# DotLight.net
KiCad netlist of a schematic drawn in EAGLE
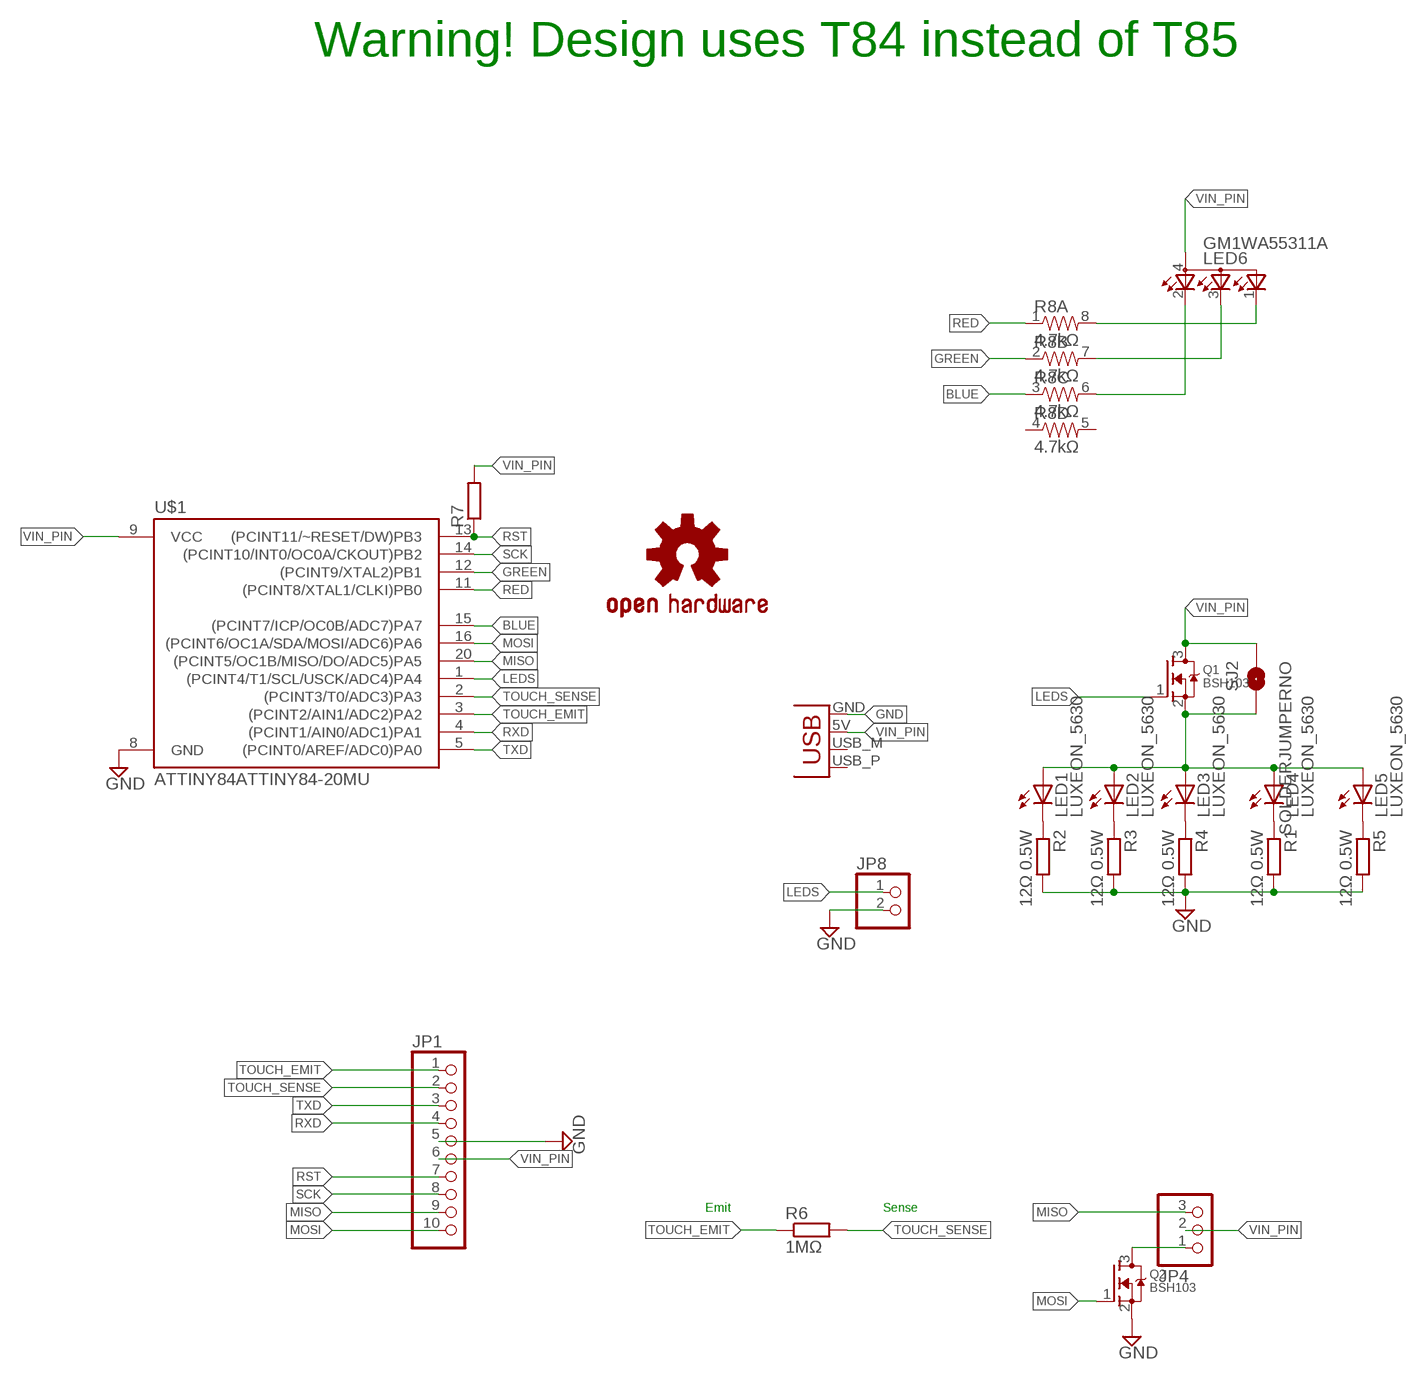
[diagram p0: schematic, sheet 1]
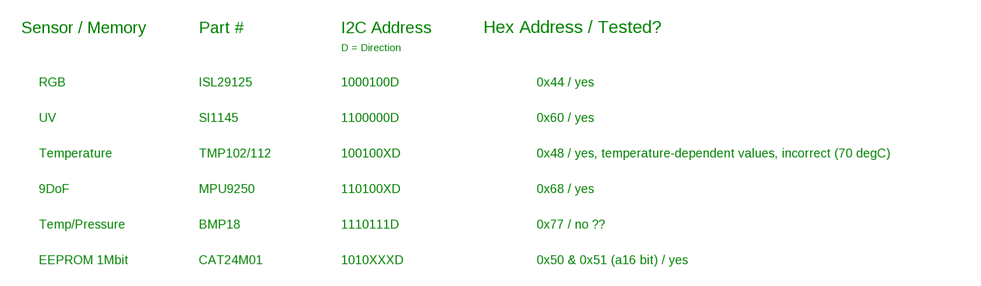
[diagram p1: schematic, sheet 2]
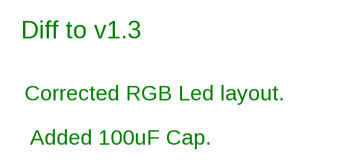
[diagram p2: schematic, sheet 3]

(export (version "E")
  (design (tool "Eeschema 10.0.6"))
  (components
    (comp (ref "JP1")
      (value "PINHD-1X10")
      (footprint "eagle-import:1X10")
      (libsource (lib "eagle-import") (part "PINHD-1X10"))
    )
    (comp (ref "JP3")
      (value "USBPCB")
      (footprint "eagle-import:USB-A-PCB")
      (libsource (lib "eagle-import") (part "USBPCB"))
    )
    (comp (ref "JP4")
      (value "PINHD-1X3")
      (footprint "eagle-import:1X03")
      (libsource (lib "eagle-import") (part "PINHD-1X3"))
    )
    (comp (ref "JP8")
      (value "PINHD-1X2")
      (footprint "eagle-import:1X02")
      (libsource (lib "eagle-import") (part "PINHD-1X2"))
    )
    (comp (ref "LED1")
      (value "LUXEON_5630")
      (footprint "eagle-import:LUXEON_5630")
      (libsource (lib "eagle-import") (part "LUXEON_5630"))
    )
    (comp (ref "LED2")
      (value "LUXEON_5630")
      (footprint "eagle-import:LUXEON_5630")
      (libsource (lib "eagle-import") (part "LUXEON_5630"))
    )
    (comp (ref "LED3")
      (value "LUXEON_5630")
      (footprint "eagle-import:LUXEON_5630")
      (libsource (lib "eagle-import") (part "LUXEON_5630"))
    )
    (comp (ref "LED4")
      (value "LUXEON_5630")
      (footprint "eagle-import:LUXEON_5630")
      (libsource (lib "eagle-import") (part "LUXEON_5630"))
    )
    (comp (ref "LED5")
      (value "LUXEON_5630")
      (footprint "eagle-import:LUXEON_5630")
      (libsource (lib "eagle-import") (part "LUXEON_5630"))
    )
    (comp (ref "LED6")
      (value "GM1WA55311A")
      (footprint "eagle-import:GM1WA55311A")
      (libsource (lib "eagle-import") (part "GM1WA55311A"))
    )
    (comp (ref "LOGO1")
      (value "OSHW-LOGOS")
      (footprint "eagle-import:OSHW-LOGO-S")
      (libsource (lib "eagle-import") (part "OSHW-LOGOS"))
    )
    (comp (ref "Q1")
      (value "BSH103")
      (footprint "eagle-import:SOT23")
      (libsource (lib "eagle-import") (part "MOSFET-NREFLOW"))
    )
    (comp (ref "Q2")
      (value "BSH103")
      (footprint "eagle-import:SOT23")
      (libsource (lib "eagle-import") (part "MOSFET-NREFLOW"))
    )
    (comp (ref "R1")
      (value "12Ω 0.5W")
      (footprint "eagle-import:R1210")
      (libsource (lib "eagle-import") (part "resistor_R-EU_R1210"))
    )
    (comp (ref "R2")
      (value "12Ω 0.5W")
      (footprint "eagle-import:R1210")
      (libsource (lib "eagle-import") (part "resistor_R-EU_R1210"))
    )
    (comp (ref "R3")
      (value "12Ω 0.5W")
      (footprint "eagle-import:R1210")
      (libsource (lib "eagle-import") (part "resistor_R-EU_R1210"))
    )
    (comp (ref "R4")
      (value "12Ω 0.5W")
      (footprint "eagle-import:R1210")
      (libsource (lib "eagle-import") (part "resistor_R-EU_R1210"))
    )
    (comp (ref "R5")
      (value "12Ω 0.5W")
      (footprint "eagle-import:R1210")
      (libsource (lib "eagle-import") (part "resistor_R-EU_R1210"))
    )
    (comp (ref "R6")
      (value "1MΩ")
      (footprint "eagle-import:R1206")
      (libsource (lib "eagle-import") (part "resistor_R-EU_R1206"))
    )
    (comp (ref "R7")
      (value "R-EU_R0603")
      (footprint "eagle-import:R0603")
      (libsource (lib "eagle-import") (part "R-EU_R0603"))
    )
    (comp (ref "R8")
      (value "4.7kΩ")
      (footprint "eagle-import:0603-ARV")
      (libsource (lib "eagle-import") (part "RESISTOR-ARRAY0603-ARV"))
    )
    (comp (ref "SJ2")
      (value "SOLDERJUMPERNO")
      (footprint "eagle-import:SJ_2S-NO")
      (libsource (lib "eagle-import") (part "SOLDERJUMPERNO"))
    )
    (comp (ref "U$1")
      (value "ATTINY84ATTINY84-20MU")
      (footprint "eagle-import:QFN20")
      (libsource (lib "eagle-import") (part "ATTINY84ATTINY84-20MU"))
    )
  )
  (nets
    (net (code "1") (name "BLUE") (class "Default")
      (node (ref "R8") (pin "3") (pinfunction "1_3") (pintype "passive"))
      (node (ref "U$1") (pin "15") (pinfunction "(PCINT7/ICP/OC0B/ADC7)PA7_15") (pintype "bidirectional"))
    )
    (net (code "2") (name "GND") (class "Default")
      (node (ref "JP1") (pin "5") (pinfunction "5_5") (pintype "passive"))
      (node (ref "JP3") (pin "GND") (pinfunction "GND_GND") (pintype "bidirectional"))
      (node (ref "JP8") (pin "2") (pinfunction "2_2") (pintype "passive"))
      (node (ref "Q2") (pin "2") (pinfunction "S_2") (pintype "bidirectional"))
      (node (ref "R1") (pin "2") (pinfunction "2_2") (pintype "passive"))
      (node (ref "R2") (pin "2") (pinfunction "2_2") (pintype "passive"))
      (node (ref "R3") (pin "2") (pinfunction "2_2") (pintype "passive"))
      (node (ref "R4") (pin "2") (pinfunction "2_2") (pintype "passive"))
      (node (ref "R5") (pin "2") (pinfunction "2_2") (pintype "passive"))
      (node (ref "U$1") (pin "8") (pinfunction "GND_8") (pintype "bidirectional"))
    )
    (net (code "3") (name "GREEN") (class "Default")
      (node (ref "R8") (pin "2") (pinfunction "1_2") (pintype "passive"))
      (node (ref "U$1") (pin "12") (pinfunction "(PCINT9/XTAL2)PB1_12") (pintype "bidirectional"))
    )
    (net (code "4") (name "LEDS") (class "Default")
      (node (ref "JP8") (pin "1") (pinfunction "1_1") (pintype "passive"))
      (node (ref "Q1") (pin "1") (pinfunction "G_1") (pintype "bidirectional"))
      (node (ref "U$1") (pin "1") (pinfunction "(PCINT4/T1/SCL/USCK/ADC4)PA4_1") (pintype "bidirectional"))
    )
    (net (code "5") (name "MISO") (class "Default")
      (node (ref "JP1") (pin "9") (pinfunction "9_9") (pintype "passive"))
      (node (ref "JP4") (pin "3") (pinfunction "3_3") (pintype "passive"))
      (node (ref "U$1") (pin "20") (pinfunction "(PCINT5/OC1B/MISO/DO/ADC5)PA5_20") (pintype "bidirectional"))
    )
    (net (code "6") (name "MOSI") (class "Default")
      (node (ref "JP1") (pin "10") (pinfunction "10_10") (pintype "passive"))
      (node (ref "Q2") (pin "1") (pinfunction "G_1") (pintype "bidirectional"))
      (node (ref "U$1") (pin "16") (pinfunction "(PCINT6/OC1A/SDA/MOSI/ADC6)PA6_16") (pintype "bidirectional"))
    )
    (net (code "7") (name "Net-(LED1-PadC)") (class "Default")
      (node (ref "LED1") (pin "C") (pinfunction "C_C") (pintype "passive"))
      (node (ref "R2") (pin "1") (pinfunction "1_1") (pintype "passive"))
    )
    (net (code "8") (name "Net-(LED2-PadC)") (class "Default")
      (node (ref "LED2") (pin "C") (pinfunction "C_C") (pintype "passive"))
      (node (ref "R3") (pin "1") (pinfunction "1_1") (pintype "passive"))
    )
    (net (code "9") (name "Net-(LED3-PadC)") (class "Default")
      (node (ref "LED3") (pin "C") (pinfunction "C_C") (pintype "passive"))
      (node (ref "R4") (pin "1") (pinfunction "1_1") (pintype "passive"))
    )
    (net (code "10") (name "Net-(LED4-PadC)") (class "Default")
      (node (ref "LED4") (pin "C") (pinfunction "C_C") (pintype "passive"))
      (node (ref "R1") (pin "1") (pinfunction "1_1") (pintype "passive"))
    )
    (net (code "11") (name "Net-(LED5-PadC)") (class "Default")
      (node (ref "LED5") (pin "C") (pinfunction "C_C") (pintype "passive"))
      (node (ref "R5") (pin "1") (pinfunction "1_1") (pintype "passive"))
    )
    (net (code "12") (name "Net-(LED6-CBLUE)") (class "Default")
      (node (ref "LED6") (pin "3") (pinfunction "CBLUE_3") (pintype "passive"))
      (node (ref "R8") (pin "7") (pinfunction "2_7") (pintype "passive"))
    )
    (net (code "13") (name "Net-(LED6-CGREEN)") (class "Default")
      (node (ref "LED6") (pin "1") (pinfunction "CGREEN_1") (pintype "passive"))
      (node (ref "R8") (pin "8") (pinfunction "2_8") (pintype "passive"))
    )
    (net (code "14") (name "Net-(LED6-CRED)") (class "Default")
      (node (ref "LED6") (pin "2") (pinfunction "CRED_2") (pintype "passive"))
      (node (ref "R8") (pin "6") (pinfunction "2_6") (pintype "passive"))
    )
    (net (code "15") (name "Net-(Q1-S)") (class "Default")
      (node (ref "LED1") (pin "A") (pinfunction "A_A") (pintype "passive"))
      (node (ref "LED2") (pin "A") (pinfunction "A_A") (pintype "passive"))
      (node (ref "LED3") (pin "A") (pinfunction "A_A") (pintype "passive"))
      (node (ref "LED4") (pin "A") (pinfunction "A_A") (pintype "passive"))
      (node (ref "LED5") (pin "A") (pinfunction "A_A") (pintype "passive"))
      (node (ref "Q1") (pin "2") (pinfunction "S_2") (pintype "bidirectional"))
      (node (ref "SJ2") (pin "2") (pinfunction "2_2") (pintype "passive"))
    )
    (net (code "16") (name "Net-(Q2-D)") (class "Default")
      (node (ref "JP4") (pin "1") (pinfunction "1_1") (pintype "passive"))
      (node (ref "Q2") (pin "3") (pinfunction "D_3") (pintype "bidirectional"))
    )
    (net (code "17") (name "RED") (class "Default")
      (node (ref "R8") (pin "1") (pinfunction "1_1") (pintype "passive"))
      (node (ref "U$1") (pin "11") (pinfunction "(PCINT8/XTAL1/CLKI)PB0_11") (pintype "bidirectional"))
    )
    (net (code "18") (name "RST") (class "Default")
      (node (ref "JP1") (pin "7") (pinfunction "7_7") (pintype "passive"))
      (node (ref "R7") (pin "1") (pinfunction "1_1") (pintype "passive"))
      (node (ref "U$1") (pin "13") (pinfunction "(PCINT11/~{RESET/DW})PB3_13") (pintype "bidirectional"))
    )
    (net (code "19") (name "RXD") (class "Default")
      (node (ref "JP1") (pin "4") (pinfunction "4_4") (pintype "passive"))
      (node (ref "U$1") (pin "4") (pinfunction "(PCINT1/AIN0/ADC1)PA1_4") (pintype "bidirectional"))
    )
    (net (code "20") (name "SCK") (class "Default")
      (node (ref "JP1") (pin "8") (pinfunction "8_8") (pintype "passive"))
      (node (ref "U$1") (pin "14") (pinfunction "(PCINT10/INT0/OC0A/CKOUT)PB2_14") (pintype "bidirectional"))
    )
    (net (code "21") (name "TOUCH_EMIT") (class "Default")
      (node (ref "JP1") (pin "1") (pinfunction "1_1") (pintype "passive"))
      (node (ref "R6") (pin "1") (pinfunction "1_1") (pintype "passive"))
      (node (ref "U$1") (pin "3") (pinfunction "(PCINT2/AIN1/ADC2)PA2_3") (pintype "bidirectional"))
    )
    (net (code "22") (name "TOUCH_SENSE") (class "Default")
      (node (ref "JP1") (pin "2") (pinfunction "2_2") (pintype "passive"))
      (node (ref "R6") (pin "2") (pinfunction "2_2") (pintype "passive"))
      (node (ref "U$1") (pin "2") (pinfunction "(PCINT3/T0/ADC3)PA3_2") (pintype "bidirectional"))
    )
    (net (code "23") (name "TXD") (class "Default")
      (node (ref "JP1") (pin "3") (pinfunction "3_3") (pintype "passive"))
      (node (ref "U$1") (pin "5") (pinfunction "(PCINT0/AREF/ADC0)PA0_5") (pintype "bidirectional"))
    )
    (net (code "24") (name "VIN_PIN") (class "Default")
      (node (ref "JP1") (pin "6") (pinfunction "6_6") (pintype "passive"))
      (node (ref "JP3") (pin "5V") (pinfunction "VBUS_5V") (pintype "bidirectional"))
      (node (ref "JP4") (pin "2") (pinfunction "2_2") (pintype "passive"))
      (node (ref "LED6") (pin "4") (pinfunction "A_4") (pintype "passive"))
      (node (ref "Q1") (pin "3") (pinfunction "D_3") (pintype "bidirectional"))
      (node (ref "R7") (pin "2") (pinfunction "2_2") (pintype "passive"))
      (node (ref "SJ2") (pin "1") (pinfunction "1_1") (pintype "passive"))
      (node (ref "U$1") (pin "9") (pinfunction "VCC_9") (pintype "bidirectional"))
    )
    (net (code "25") (name "unconnected-(JP3-D+-PadUSB_P)") (class "Default")
      (node (ref "JP3") (pin "USB_P") (pinfunction "D+_USB_P") (pintype "bidirectional"))
    )
    (net (code "26") (name "unconnected-(JP3-D--PadUSB_M)") (class "Default")
      (node (ref "JP3") (pin "USB_M") (pinfunction "D-_USB_M") (pintype "bidirectional"))
    )
    (net (code "27") (name "unconnected-(R8D-1-Pad4)") (class "Default")
      (node (ref "R8") (pin "4") (pinfunction "1_4") (pintype "passive"))
    )
    (net (code "28") (name "unconnected-(R8D-2-Pad5)") (class "Default")
      (node (ref "R8") (pin "5") (pinfunction "2_5") (pintype "passive"))
    )
  )
)
